# M900.net
KiCad netlist of a schematic drawn in EAGLE
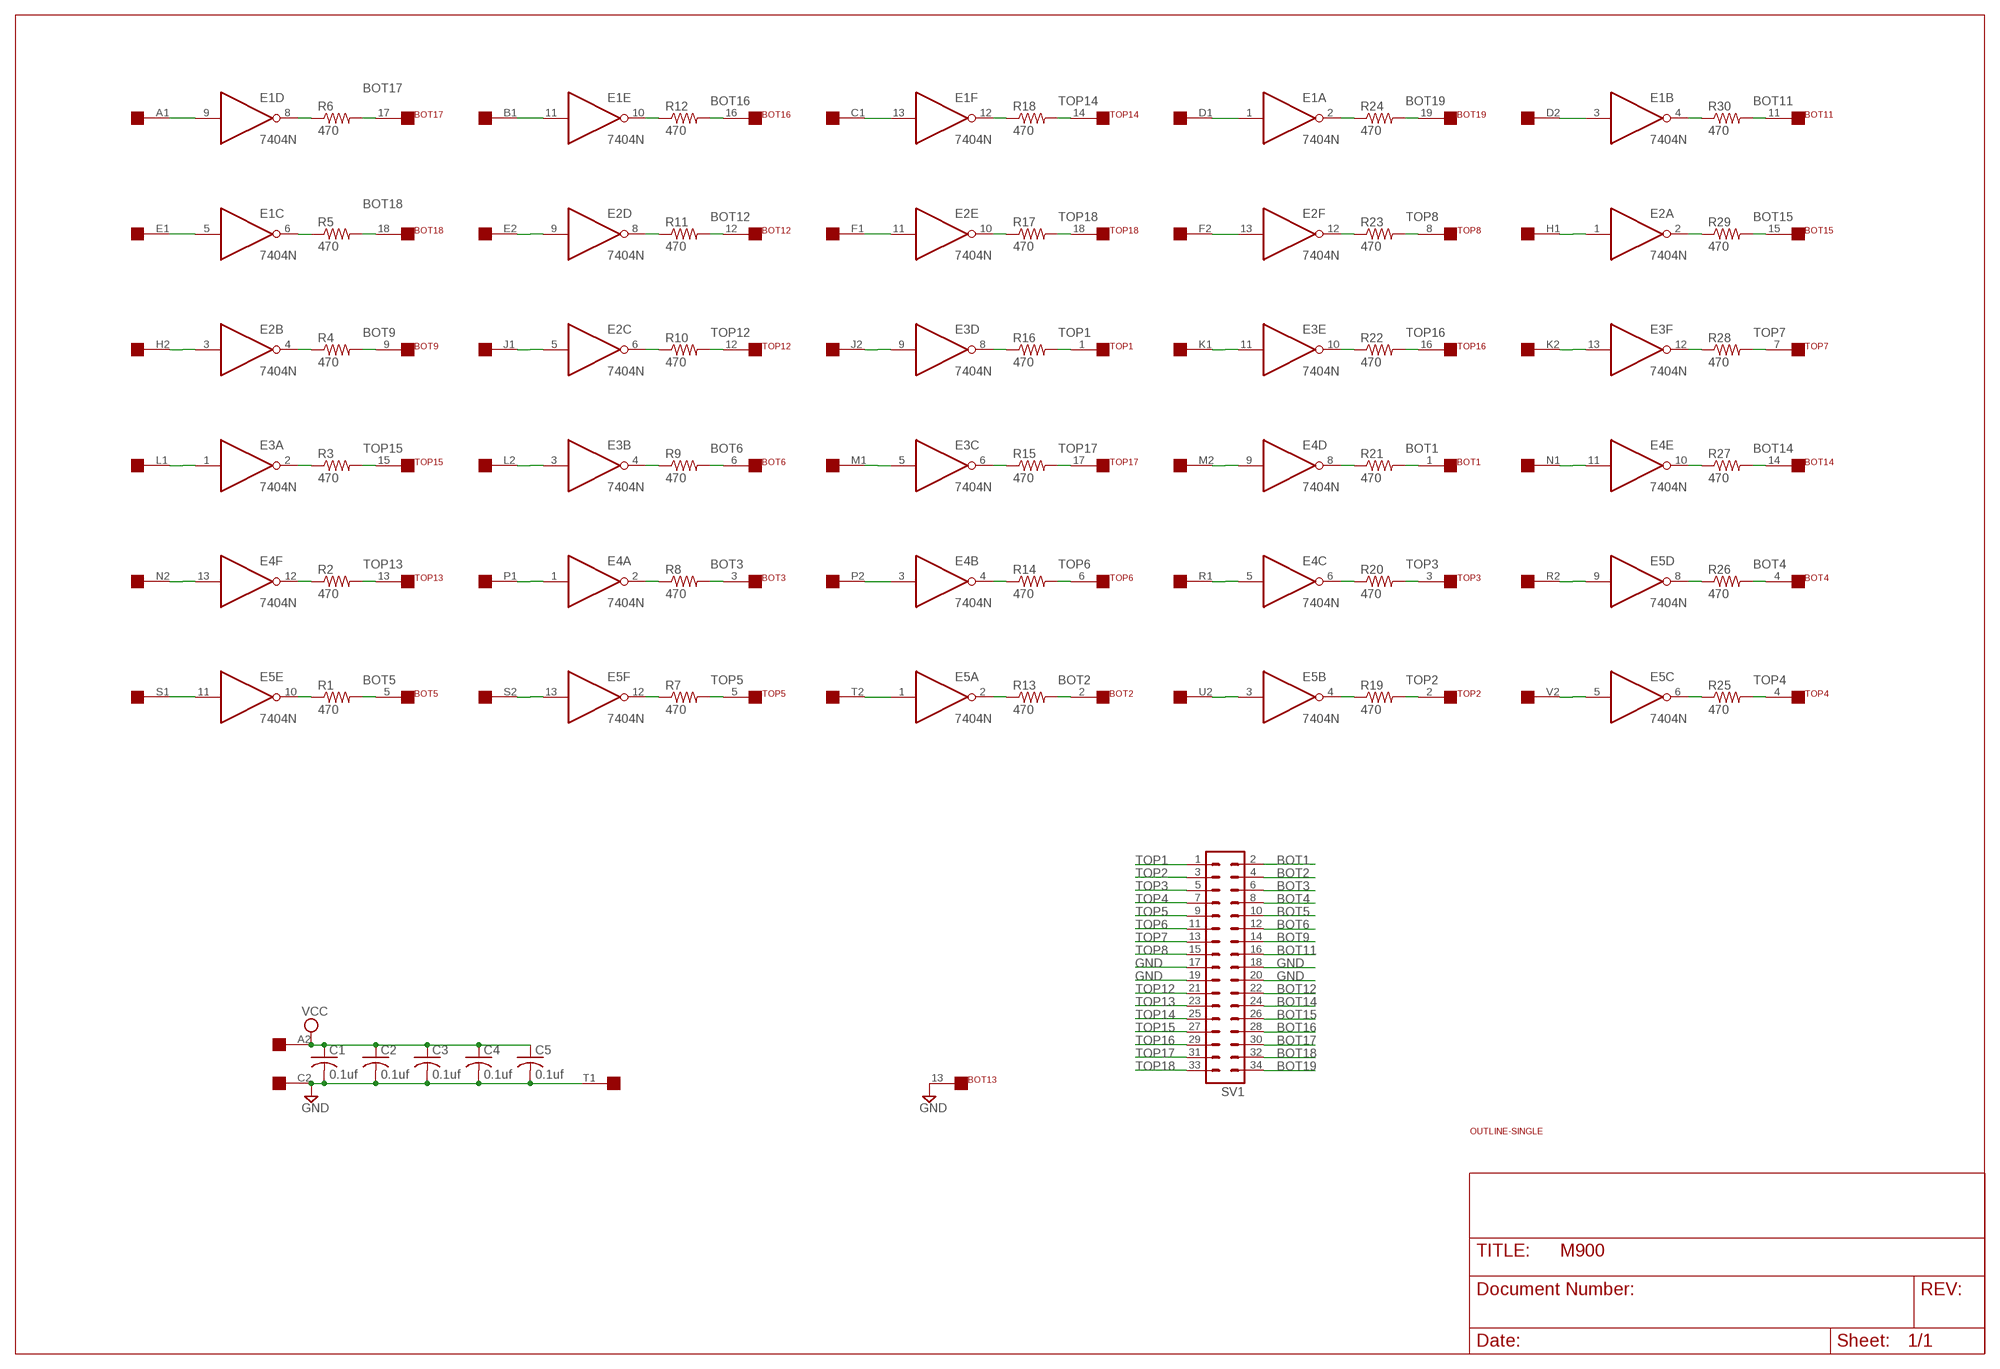
[diagram p0: schematic, sheet 1]

(export (version "E")
  (design (tool "Eeschema 10.0.6"))
  (components
    (comp (ref "BOT")
      (value "FLEX19")
      (footprint "eagle-import:FLEX19")
      (libsource (lib "eagle-import") (part "FLEX19"))
    )
    (comp (ref "C1")
      (value "0.1uf")
      (footprint "eagle-import:C050-025X075")
      (libsource (lib "eagle-import") (part "C-US050-025X075"))
    )
    (comp (ref "C2")
      (value "0.1uf")
      (footprint "eagle-import:C050-025X075")
      (libsource (lib "eagle-import") (part "C-US050-025X075"))
    )
    (comp (ref "C3")
      (value "0.1uf")
      (footprint "eagle-import:C050-025X075")
      (libsource (lib "eagle-import") (part "C-US050-025X075"))
    )
    (comp (ref "C4")
      (value "0.1uf")
      (footprint "eagle-import:C050-025X075")
      (libsource (lib "eagle-import") (part "C-US050-025X075"))
    )
    (comp (ref "C5")
      (value "0.1uf")
      (footprint "eagle-import:C050-025X075")
      (libsource (lib "eagle-import") (part "C-US050-025X075"))
    )
    (comp (ref "E1")
      (value "7404N")
      (footprint "eagle-import:DIL14")
      (libsource (lib "eagle-import") (part "7404N"))
    )
    (comp (ref "E2")
      (value "7404N")
      (footprint "eagle-import:DIL14")
      (libsource (lib "eagle-import") (part "7404N"))
    )
    (comp (ref "E3")
      (value "7404N")
      (footprint "eagle-import:DIL14")
      (libsource (lib "eagle-import") (part "7404N"))
    )
    (comp (ref "E4")
      (value "7404N")
      (footprint "eagle-import:DIL14")
      (libsource (lib "eagle-import") (part "7404N"))
    )
    (comp (ref "E5")
      (value "7404N")
      (footprint "eagle-import:DIL14")
      (libsource (lib "eagle-import") (part "7404N"))
    )
    (comp (ref "EDGE")
      (value "SINGLE")
      (footprint "eagle-import:EDGE-CON2")
      (libsource (lib "eagle-import") (part "SINGLE"))
    )
    (comp (ref "R1")
      (value "470")
      (footprint "eagle-import:0207_10")
      (libsource (lib "eagle-import") (part "R-US_0207/10"))
    )
    (comp (ref "R2")
      (value "470")
      (footprint "eagle-import:0207_10")
      (libsource (lib "eagle-import") (part "R-US_0207/10"))
    )
    (comp (ref "R3")
      (value "470")
      (footprint "eagle-import:0207_10")
      (libsource (lib "eagle-import") (part "R-US_0207/10"))
    )
    (comp (ref "R4")
      (value "470")
      (footprint "eagle-import:0207_10")
      (libsource (lib "eagle-import") (part "R-US_0207/10"))
    )
    (comp (ref "R5")
      (value "470")
      (footprint "eagle-import:0207_10")
      (libsource (lib "eagle-import") (part "R-US_0207/10"))
    )
    (comp (ref "R6")
      (value "470")
      (footprint "eagle-import:0207_10")
      (libsource (lib "eagle-import") (part "R-US_0207/10"))
    )
    (comp (ref "R7")
      (value "470")
      (footprint "eagle-import:0207_10")
      (libsource (lib "eagle-import") (part "R-US_0207/10"))
    )
    (comp (ref "R8")
      (value "470")
      (footprint "eagle-import:0207_10")
      (libsource (lib "eagle-import") (part "R-US_0207/10"))
    )
    (comp (ref "R9")
      (value "470")
      (footprint "eagle-import:0207_10")
      (libsource (lib "eagle-import") (part "R-US_0207/10"))
    )
    (comp (ref "R10")
      (value "470")
      (footprint "eagle-import:0207_10")
      (libsource (lib "eagle-import") (part "R-US_0207/10"))
    )
    (comp (ref "R11")
      (value "470")
      (footprint "eagle-import:0207_10")
      (libsource (lib "eagle-import") (part "R-US_0207/10"))
    )
    (comp (ref "R12")
      (value "470")
      (footprint "eagle-import:0207_10")
      (libsource (lib "eagle-import") (part "R-US_0207/10"))
    )
    (comp (ref "R13")
      (value "470")
      (footprint "eagle-import:0207_10")
      (libsource (lib "eagle-import") (part "R-US_0207/10"))
    )
    (comp (ref "R14")
      (value "470")
      (footprint "eagle-import:0207_10")
      (libsource (lib "eagle-import") (part "R-US_0207/10"))
    )
    (comp (ref "R15")
      (value "470")
      (footprint "eagle-import:0207_10")
      (libsource (lib "eagle-import") (part "R-US_0207/10"))
    )
    (comp (ref "R16")
      (value "470")
      (footprint "eagle-import:0207_10")
      (libsource (lib "eagle-import") (part "R-US_0207/10"))
    )
    (comp (ref "R17")
      (value "470")
      (footprint "eagle-import:0207_10")
      (libsource (lib "eagle-import") (part "R-US_0207/10"))
    )
    (comp (ref "R18")
      (value "470")
      (footprint "eagle-import:0207_10")
      (libsource (lib "eagle-import") (part "R-US_0207/10"))
    )
    (comp (ref "R19")
      (value "470")
      (footprint "eagle-import:0207_10")
      (libsource (lib "eagle-import") (part "R-US_0207/10"))
    )
    (comp (ref "R20")
      (value "470")
      (footprint "eagle-import:0207_10")
      (libsource (lib "eagle-import") (part "R-US_0207/10"))
    )
    (comp (ref "R21")
      (value "470")
      (footprint "eagle-import:0207_10")
      (libsource (lib "eagle-import") (part "R-US_0207/10"))
    )
    (comp (ref "R22")
      (value "470")
      (footprint "eagle-import:0207_10")
      (libsource (lib "eagle-import") (part "R-US_0207/10"))
    )
    (comp (ref "R23")
      (value "470")
      (footprint "eagle-import:0207_10")
      (libsource (lib "eagle-import") (part "R-US_0207/10"))
    )
    (comp (ref "R24")
      (value "470")
      (footprint "eagle-import:0207_10")
      (libsource (lib "eagle-import") (part "R-US_0207/10"))
    )
    (comp (ref "R25")
      (value "470")
      (footprint "eagle-import:0207_10")
      (libsource (lib "eagle-import") (part "R-US_0207/10"))
    )
    (comp (ref "R26")
      (value "470")
      (footprint "eagle-import:0207_10")
      (libsource (lib "eagle-import") (part "R-US_0207/10"))
    )
    (comp (ref "R27")
      (value "470")
      (footprint "eagle-import:0207_10")
      (libsource (lib "eagle-import") (part "R-US_0207/10"))
    )
    (comp (ref "R28")
      (value "470")
      (footprint "eagle-import:0207_10")
      (libsource (lib "eagle-import") (part "R-US_0207/10"))
    )
    (comp (ref "R29")
      (value "470")
      (footprint "eagle-import:0207_10")
      (libsource (lib "eagle-import") (part "R-US_0207/10"))
    )
    (comp (ref "R30")
      (value "470")
      (footprint "eagle-import:0207_10")
      (libsource (lib "eagle-import") (part "R-US_0207/10"))
    )
    (comp (ref "SV1")
      (value "MA17-2")
      (footprint "eagle-import:MA17-2")
      (libsource (lib "eagle-import") (part "MA17-2"))
    )
    (comp (ref "TOP")
      (value "FLEX19")
      (footprint "eagle-import:FLEX19")
      (libsource (lib "eagle-import") (part "FLEX19"))
    )
    (comp (ref "U$2")
      (value "OUTLINE-SINGLE")
      (footprint "eagle-import:SINGLE")
      (libsource (lib "eagle-import") (part "OUTLINE-SINGLE"))
    )
  )
  (nets
    (net (code "1") (name "/BOT1") (class "Default")
      (node (ref "BOT") (pin "1") (pinfunction "1_1") (pintype "passive"))
      (node (ref "R21") (pin "2") (pinfunction "2_2") (pintype "passive"))
      (node (ref "SV1") (pin "2") (pinfunction "2_2") (pintype "passive"))
    )
    (net (code "2") (name "/BOT2") (class "Default")
      (node (ref "BOT") (pin "2") (pinfunction "1_2") (pintype "passive"))
      (node (ref "R13") (pin "2") (pinfunction "2_2") (pintype "passive"))
      (node (ref "SV1") (pin "4") (pinfunction "4_4") (pintype "passive"))
    )
    (net (code "3") (name "/BOT3") (class "Default")
      (node (ref "BOT") (pin "3") (pinfunction "1_3") (pintype "passive"))
      (node (ref "R8") (pin "2") (pinfunction "2_2") (pintype "passive"))
      (node (ref "SV1") (pin "6") (pinfunction "6_6") (pintype "passive"))
    )
    (net (code "4") (name "/BOT4") (class "Default")
      (node (ref "BOT") (pin "4") (pinfunction "1_4") (pintype "passive"))
      (node (ref "R26") (pin "2") (pinfunction "2_2") (pintype "passive"))
      (node (ref "SV1") (pin "8") (pinfunction "8_8") (pintype "passive"))
    )
    (net (code "5") (name "/BOT5") (class "Default")
      (node (ref "BOT") (pin "5") (pinfunction "1_5") (pintype "passive"))
      (node (ref "R1") (pin "2") (pinfunction "2_2") (pintype "passive"))
      (node (ref "SV1") (pin "10") (pinfunction "10_10") (pintype "passive"))
    )
    (net (code "6") (name "/BOT6") (class "Default")
      (node (ref "BOT") (pin "6") (pinfunction "1_6") (pintype "passive"))
      (node (ref "R9") (pin "2") (pinfunction "2_2") (pintype "passive"))
      (node (ref "SV1") (pin "12") (pinfunction "12_12") (pintype "passive"))
    )
    (net (code "7") (name "/BOT9") (class "Default")
      (node (ref "BOT") (pin "9") (pinfunction "1_9") (pintype "passive"))
      (node (ref "R4") (pin "2") (pinfunction "2_2") (pintype "passive"))
      (node (ref "SV1") (pin "14") (pinfunction "14_14") (pintype "passive"))
    )
    (net (code "8") (name "/BOT11") (class "Default")
      (node (ref "BOT") (pin "11") (pinfunction "1_11") (pintype "passive"))
      (node (ref "R30") (pin "2") (pinfunction "2_2") (pintype "passive"))
      (node (ref "SV1") (pin "16") (pinfunction "16_16") (pintype "passive"))
    )
    (net (code "9") (name "/BOT12") (class "Default")
      (node (ref "BOT") (pin "12") (pinfunction "1_12") (pintype "passive"))
      (node (ref "R11") (pin "2") (pinfunction "2_2") (pintype "passive"))
      (node (ref "SV1") (pin "22") (pinfunction "22_22") (pintype "passive"))
    )
    (net (code "10") (name "/BOT14") (class "Default")
      (node (ref "BOT") (pin "14") (pinfunction "1_14") (pintype "passive"))
      (node (ref "R27") (pin "2") (pinfunction "2_2") (pintype "passive"))
      (node (ref "SV1") (pin "24") (pinfunction "24_24") (pintype "passive"))
    )
    (net (code "11") (name "/BOT15") (class "Default")
      (node (ref "BOT") (pin "15") (pinfunction "1_15") (pintype "passive"))
      (node (ref "R29") (pin "2") (pinfunction "2_2") (pintype "passive"))
      (node (ref "SV1") (pin "26") (pinfunction "26_26") (pintype "passive"))
    )
    (net (code "12") (name "/BOT16") (class "Default")
      (node (ref "BOT") (pin "16") (pinfunction "1_16") (pintype "passive"))
      (node (ref "R12") (pin "2") (pinfunction "2_2") (pintype "passive"))
      (node (ref "SV1") (pin "28") (pinfunction "28_28") (pintype "passive"))
    )
    (net (code "13") (name "/BOT17") (class "Default")
      (node (ref "BOT") (pin "17") (pinfunction "1_17") (pintype "passive"))
      (node (ref "R6") (pin "2") (pinfunction "2_2") (pintype "passive"))
      (node (ref "SV1") (pin "30") (pinfunction "30_30") (pintype "passive"))
    )
    (net (code "14") (name "/BOT18") (class "Default")
      (node (ref "BOT") (pin "18") (pinfunction "1_18") (pintype "passive"))
      (node (ref "R5") (pin "2") (pinfunction "2_2") (pintype "passive"))
      (node (ref "SV1") (pin "32") (pinfunction "32_32") (pintype "passive"))
    )
    (net (code "15") (name "/BOT19") (class "Default")
      (node (ref "BOT") (pin "19") (pinfunction "1_19") (pintype "passive"))
      (node (ref "R24") (pin "2") (pinfunction "2_2") (pintype "passive"))
      (node (ref "SV1") (pin "34") (pinfunction "34_34") (pintype "passive"))
    )
    (net (code "16") (name "/TOP1") (class "Default")
      (node (ref "R16") (pin "2") (pinfunction "2_2") (pintype "passive"))
      (node (ref "SV1") (pin "1") (pinfunction "1_1") (pintype "passive"))
      (node (ref "TOP") (pin "1") (pinfunction "1_1") (pintype "passive"))
    )
    (net (code "17") (name "/TOP2") (class "Default")
      (node (ref "R19") (pin "2") (pinfunction "2_2") (pintype "passive"))
      (node (ref "SV1") (pin "3") (pinfunction "3_3") (pintype "passive"))
      (node (ref "TOP") (pin "2") (pinfunction "1_2") (pintype "passive"))
    )
    (net (code "18") (name "/TOP3") (class "Default")
      (node (ref "R20") (pin "2") (pinfunction "2_2") (pintype "passive"))
      (node (ref "SV1") (pin "5") (pinfunction "5_5") (pintype "passive"))
      (node (ref "TOP") (pin "3") (pinfunction "1_3") (pintype "passive"))
    )
    (net (code "19") (name "/TOP4") (class "Default")
      (node (ref "R25") (pin "2") (pinfunction "2_2") (pintype "passive"))
      (node (ref "SV1") (pin "7") (pinfunction "7_7") (pintype "passive"))
      (node (ref "TOP") (pin "4") (pinfunction "1_4") (pintype "passive"))
    )
    (net (code "20") (name "/TOP5") (class "Default")
      (node (ref "R7") (pin "2") (pinfunction "2_2") (pintype "passive"))
      (node (ref "SV1") (pin "9") (pinfunction "9_9") (pintype "passive"))
      (node (ref "TOP") (pin "5") (pinfunction "1_5") (pintype "passive"))
    )
    (net (code "21") (name "/TOP6") (class "Default")
      (node (ref "R14") (pin "2") (pinfunction "2_2") (pintype "passive"))
      (node (ref "SV1") (pin "11") (pinfunction "11_11") (pintype "passive"))
      (node (ref "TOP") (pin "6") (pinfunction "1_6") (pintype "passive"))
    )
    (net (code "22") (name "/TOP7") (class "Default")
      (node (ref "R28") (pin "2") (pinfunction "2_2") (pintype "passive"))
      (node (ref "SV1") (pin "13") (pinfunction "13_13") (pintype "passive"))
      (node (ref "TOP") (pin "7") (pinfunction "1_7") (pintype "passive"))
    )
    (net (code "23") (name "/TOP8") (class "Default")
      (node (ref "R23") (pin "2") (pinfunction "2_2") (pintype "passive"))
      (node (ref "SV1") (pin "15") (pinfunction "15_15") (pintype "passive"))
      (node (ref "TOP") (pin "8") (pinfunction "1_8") (pintype "passive"))
    )
    (net (code "24") (name "/TOP12") (class "Default")
      (node (ref "R10") (pin "2") (pinfunction "2_2") (pintype "passive"))
      (node (ref "SV1") (pin "21") (pinfunction "21_21") (pintype "passive"))
      (node (ref "TOP") (pin "12") (pinfunction "1_12") (pintype "passive"))
    )
    (net (code "25") (name "/TOP13") (class "Default")
      (node (ref "R2") (pin "2") (pinfunction "2_2") (pintype "passive"))
      (node (ref "SV1") (pin "23") (pinfunction "23_23") (pintype "passive"))
      (node (ref "TOP") (pin "13") (pinfunction "1_13") (pintype "passive"))
    )
    (net (code "26") (name "/TOP14") (class "Default")
      (node (ref "R18") (pin "2") (pinfunction "2_2") (pintype "passive"))
      (node (ref "SV1") (pin "25") (pinfunction "25_25") (pintype "passive"))
      (node (ref "TOP") (pin "14") (pinfunction "1_14") (pintype "passive"))
    )
    (net (code "27") (name "/TOP15") (class "Default")
      (node (ref "R3") (pin "2") (pinfunction "2_2") (pintype "passive"))
      (node (ref "SV1") (pin "27") (pinfunction "27_27") (pintype "passive"))
      (node (ref "TOP") (pin "15") (pinfunction "1_15") (pintype "passive"))
    )
    (net (code "28") (name "/TOP16") (class "Default")
      (node (ref "R22") (pin "2") (pinfunction "2_2") (pintype "passive"))
      (node (ref "SV1") (pin "29") (pinfunction "29_29") (pintype "passive"))
      (node (ref "TOP") (pin "16") (pinfunction "1_16") (pintype "passive"))
    )
    (net (code "29") (name "/TOP17") (class "Default")
      (node (ref "R15") (pin "2") (pinfunction "2_2") (pintype "passive"))
      (node (ref "SV1") (pin "31") (pinfunction "31_31") (pintype "passive"))
      (node (ref "TOP") (pin "17") (pinfunction "1_17") (pintype "passive"))
    )
    (net (code "30") (name "/TOP18") (class "Default")
      (node (ref "R17") (pin "2") (pinfunction "2_2") (pintype "passive"))
      (node (ref "SV1") (pin "33") (pinfunction "33_33") (pintype "passive"))
      (node (ref "TOP") (pin "18") (pinfunction "1_18") (pintype "passive"))
    )
    (net (code "31") (name "GND") (class "Default")
      (node (ref "BOT") (pin "13") (pinfunction "1_13") (pintype "passive"))
      (node (ref "C1") (pin "2") (pinfunction "2_2") (pintype "passive"))
      (node (ref "C2") (pin "2") (pinfunction "2_2") (pintype "passive"))
      (node (ref "C3") (pin "2") (pinfunction "2_2") (pintype "passive"))
      (node (ref "C4") (pin "2") (pinfunction "2_2") (pintype "passive"))
      (node (ref "C5") (pin "2") (pinfunction "2_2") (pintype "passive"))
      (node (ref "EDGE") (pin "C2") (pinfunction "1_C2") (pintype "bidirectional"))
      (node (ref "EDGE") (pin "T1") (pinfunction "1_T1") (pintype "bidirectional"))
      (node (ref "SV1") (pin "17") (pinfunction "17_17") (pintype "passive"))
      (node (ref "SV1") (pin "18") (pinfunction "18_18") (pintype "passive"))
      (node (ref "SV1") (pin "19") (pinfunction "19_19") (pintype "passive"))
      (node (ref "SV1") (pin "20") (pinfunction "20_20") (pintype "passive"))
    )
    (net (code "32") (name "Net-(E1A-I)") (class "Default")
      (node (ref "E1") (pin "1") (pinfunction "I_1") (pintype "input"))
      (node (ref "EDGE") (pin "D1") (pinfunction "1_D1") (pintype "bidirectional"))
    )
    (net (code "33") (name "Net-(E1A-O)") (class "Default")
      (node (ref "E1") (pin "2") (pinfunction "O_2") (pintype "output"))
      (node (ref "R24") (pin "1") (pinfunction "1_1") (pintype "passive"))
    )
    (net (code "34") (name "Net-(E1B-I)") (class "Default")
      (node (ref "E1") (pin "3") (pinfunction "I_3") (pintype "input"))
      (node (ref "EDGE") (pin "D2") (pinfunction "1_D2") (pintype "bidirectional"))
    )
    (net (code "35") (name "Net-(E1B-O)") (class "Default")
      (node (ref "E1") (pin "4") (pinfunction "O_4") (pintype "output"))
      (node (ref "R30") (pin "1") (pinfunction "1_1") (pintype "passive"))
    )
    (net (code "36") (name "Net-(E1C-I)") (class "Default")
      (node (ref "E1") (pin "5") (pinfunction "I_5") (pintype "input"))
      (node (ref "EDGE") (pin "E1") (pinfunction "1_E1") (pintype "bidirectional"))
    )
    (net (code "37") (name "Net-(E1C-O)") (class "Default")
      (node (ref "E1") (pin "6") (pinfunction "O_6") (pintype "output"))
      (node (ref "R5") (pin "1") (pinfunction "1_1") (pintype "passive"))
    )
    (net (code "38") (name "Net-(E1D-I)") (class "Default")
      (node (ref "E1") (pin "9") (pinfunction "I_9") (pintype "input"))
      (node (ref "EDGE") (pin "A1") (pinfunction "1_A1") (pintype "bidirectional"))
    )
    (net (code "39") (name "Net-(E1D-O)") (class "Default")
      (node (ref "E1") (pin "8") (pinfunction "O_8") (pintype "output"))
      (node (ref "R6") (pin "1") (pinfunction "1_1") (pintype "passive"))
    )
    (net (code "40") (name "Net-(E1E-I)") (class "Default")
      (node (ref "E1") (pin "11") (pinfunction "I_11") (pintype "input"))
      (node (ref "EDGE") (pin "B1") (pinfunction "1_B1") (pintype "bidirectional"))
    )
    (net (code "41") (name "Net-(E1E-O)") (class "Default")
      (node (ref "E1") (pin "10") (pinfunction "O_10") (pintype "output"))
      (node (ref "R12") (pin "1") (pinfunction "1_1") (pintype "passive"))
    )
    (net (code "42") (name "Net-(E1F-I)") (class "Default")
      (node (ref "E1") (pin "13") (pinfunction "I_13") (pintype "input"))
      (node (ref "EDGE") (pin "C1") (pinfunction "1_C1") (pintype "bidirectional"))
    )
    (net (code "43") (name "Net-(E1F-O)") (class "Default")
      (node (ref "E1") (pin "12") (pinfunction "O_12") (pintype "output"))
      (node (ref "R18") (pin "1") (pinfunction "1_1") (pintype "passive"))
    )
    (net (code "44") (name "Net-(E2A-I)") (class "Default")
      (node (ref "E2") (pin "1") (pinfunction "I_1") (pintype "input"))
      (node (ref "EDGE") (pin "H1") (pinfunction "1_H1") (pintype "bidirectional"))
    )
    (net (code "45") (name "Net-(E2A-O)") (class "Default")
      (node (ref "E2") (pin "2") (pinfunction "O_2") (pintype "output"))
      (node (ref "R29") (pin "1") (pinfunction "1_1") (pintype "passive"))
    )
    (net (code "46") (name "Net-(E2B-I)") (class "Default")
      (node (ref "E2") (pin "3") (pinfunction "I_3") (pintype "input"))
      (node (ref "EDGE") (pin "H2") (pinfunction "1_H2") (pintype "bidirectional"))
    )
    (net (code "47") (name "Net-(E2B-O)") (class "Default")
      (node (ref "E2") (pin "4") (pinfunction "O_4") (pintype "output"))
      (node (ref "R4") (pin "1") (pinfunction "1_1") (pintype "passive"))
    )
    (net (code "48") (name "Net-(E2C-I)") (class "Default")
      (node (ref "E2") (pin "5") (pinfunction "I_5") (pintype "input"))
      (node (ref "EDGE") (pin "J1") (pinfunction "1_J1") (pintype "bidirectional"))
    )
    (net (code "49") (name "Net-(E2C-O)") (class "Default")
      (node (ref "E2") (pin "6") (pinfunction "O_6") (pintype "output"))
      (node (ref "R10") (pin "1") (pinfunction "1_1") (pintype "passive"))
    )
    (net (code "50") (name "Net-(E2D-I)") (class "Default")
      (node (ref "E2") (pin "9") (pinfunction "I_9") (pintype "input"))
      (node (ref "EDGE") (pin "E2") (pinfunction "1_E2") (pintype "bidirectional"))
    )
    (net (code "51") (name "Net-(E2D-O)") (class "Default")
      (node (ref "E2") (pin "8") (pinfunction "O_8") (pintype "output"))
      (node (ref "R11") (pin "1") (pinfunction "1_1") (pintype "passive"))
    )
    (net (code "52") (name "Net-(E2E-I)") (class "Default")
      (node (ref "E2") (pin "11") (pinfunction "I_11") (pintype "input"))
      (node (ref "EDGE") (pin "F1") (pinfunction "1_F1") (pintype "bidirectional"))
    )
    (net (code "53") (name "Net-(E2E-O)") (class "Default")
      (node (ref "E2") (pin "10") (pinfunction "O_10") (pintype "output"))
      (node (ref "R17") (pin "1") (pinfunction "1_1") (pintype "passive"))
    )
    (net (code "54") (name "Net-(E2F-I)") (class "Default")
      (node (ref "E2") (pin "13") (pinfunction "I_13") (pintype "input"))
      (node (ref "EDGE") (pin "F2") (pinfunction "1_F2") (pintype "bidirectional"))
    )
    (net (code "55") (name "Net-(E2F-O)") (class "Default")
      (node (ref "E2") (pin "12") (pinfunction "O_12") (pintype "output"))
      (node (ref "R23") (pin "1") (pinfunction "1_1") (pintype "passive"))
    )
    (net (code "56") (name "Net-(E3A-I)") (class "Default")
      (node (ref "E3") (pin "1") (pinfunction "I_1") (pintype "input"))
      (node (ref "EDGE") (pin "L1") (pinfunction "1_L1") (pintype "bidirectional"))
    )
    (net (code "57") (name "Net-(E3A-O)") (class "Default")
      (node (ref "E3") (pin "2") (pinfunction "O_2") (pintype "output"))
      (node (ref "R3") (pin "1") (pinfunction "1_1") (pintype "passive"))
    )
    (net (code "58") (name "Net-(E3B-I)") (class "Default")
      (node (ref "E3") (pin "3") (pinfunction "I_3") (pintype "input"))
      (node (ref "EDGE") (pin "L2") (pinfunction "1_L2") (pintype "bidirectional"))
    )
    (net (code "59") (name "Net-(E3B-O)") (class "Default")
      (node (ref "E3") (pin "4") (pinfunction "O_4") (pintype "output"))
      (node (ref "R9") (pin "1") (pinfunction "1_1") (pintype "passive"))
    )
    (net (code "60") (name "Net-(E3C-I)") (class "Default")
      (node (ref "E3") (pin "5") (pinfunction "I_5") (pintype "input"))
      (node (ref "EDGE") (pin "M1") (pinfunction "1_M1") (pintype "bidirectional"))
    )
    (net (code "61") (name "Net-(E3C-O)") (class "Default")
      (node (ref "E3") (pin "6") (pinfunction "O_6") (pintype "output"))
      (node (ref "R15") (pin "1") (pinfunction "1_1") (pintype "passive"))
    )
    (net (code "62") (name "Net-(E3D-I)") (class "Default")
      (node (ref "E3") (pin "9") (pinfunction "I_9") (pintype "input"))
      (node (ref "EDGE") (pin "J2") (pinfunction "1_J2") (pintype "bidirectional"))
    )
    (net (code "63") (name "Net-(E3D-O)") (class "Default")
      (node (ref "E3") (pin "8") (pinfunction "O_8") (pintype "output"))
      (node (ref "R16") (pin "1") (pinfunction "1_1") (pintype "passive"))
    )
    (net (code "64") (name "Net-(E3E-I)") (class "Default")
      (node (ref "E3") (pin "11") (pinfunction "I_11") (pintype "input"))
      (node (ref "EDGE") (pin "K1") (pinfunction "1_K1") (pintype "bidirectional"))
    )
    (net (code "65") (name "Net-(E3E-O)") (class "Default")
      (node (ref "E3") (pin "10") (pinfunction "O_10") (pintype "output"))
      (node (ref "R22") (pin "1") (pinfunction "1_1") (pintype "passive"))
    )
    (net (code "66") (name "Net-(E3F-I)") (class "Default")
      (node (ref "E3") (pin "13") (pinfunction "I_13") (pintype "input"))
      (node (ref "EDGE") (pin "K2") (pinfunction "1_K2") (pintype "bidirectional"))
    )
    (net (code "67") (name "Net-(E3F-O)") (class "Default")
      (node (ref "E3") (pin "12") (pinfunction "O_12") (pintype "output"))
      (node (ref "R28") (pin "1") (pinfunction "1_1") (pintype "passive"))
    )
    (net (code "68") (name "Net-(E4A-I)") (class "Default")
      (node (ref "E4") (pin "1") (pinfunction "I_1") (pintype "input"))
      (node (ref "EDGE") (pin "P1") (pinfunction "1_P1") (pintype "bidirectional"))
    )
    (net (code "69") (name "Net-(E4A-O)") (class "Default")
      (node (ref "E4") (pin "2") (pinfunction "O_2") (pintype "output"))
      (node (ref "R8") (pin "1") (pinfunction "1_1") (pintype "passive"))
    )
    (net (code "70") (name "Net-(E4B-I)") (class "Default")
      (node (ref "E4") (pin "3") (pinfunction "I_3") (pintype "input"))
      (node (ref "EDGE") (pin "P2") (pinfunction "1_P2") (pintype "bidirectional"))
    )
    (net (code "71") (name "Net-(E4B-O)") (class "Default")
      (node (ref "E4") (pin "4") (pinfunction "O_4") (pintype "output"))
      (node (ref "R14") (pin "1") (pinfunction "1_1") (pintype "passive"))
    )
    (net (code "72") (name "Net-(E4C-I)") (class "Default")
      (node (ref "E4") (pin "5") (pinfunction "I_5") (pintype "input"))
      (node (ref "EDGE") (pin "R1") (pinfunction "1_R1") (pintype "bidirectional"))
    )
    (net (code "73") (name "Net-(E4C-O)") (class "Default")
      (node (ref "E4") (pin "6") (pinfunction "O_6") (pintype "output"))
      (node (ref "R20") (pin "1") (pinfunction "1_1") (pintype "passive"))
    )
    (net (code "74") (name "Net-(E4D-I)") (class "Default")
      (node (ref "E4") (pin "9") (pinfunction "I_9") (pintype "input"))
      (node (ref "EDGE") (pin "M2") (pinfunction "1_M2") (pintype "bidirectional"))
    )
    (net (code "75") (name "Net-(E4D-O)") (class "Default")
      (node (ref "E4") (pin "8") (pinfunction "O_8") (pintype "output"))
      (node (ref "R21") (pin "1") (pinfunction "1_1") (pintype "passive"))
    )
    (net (code "76") (name "Net-(E4E-I)") (class "Default")
      (node (ref "E4") (pin "11") (pinfunction "I_11") (pintype "input"))
      (node (ref "EDGE") (pin "N1") (pinfunction "1_N1") (pintype "bidirectional"))
    )
    (net (code "77") (name "Net-(E4E-O)") (class "Default")
      (node (ref "E4") (pin "10") (pinfunction "O_10") (pintype "output"))
      (node (ref "R27") (pin "1") (pinfunction "1_1") (pintype "passive"))
    )
    (net (code "78") (name "Net-(E4F-I)") (class "Default")
      (node (ref "E4") (pin "13") (pinfunction "I_13") (pintype "input"))
      (node (ref "EDGE") (pin "N2") (pinfunction "1_N2") (pintype "bidirectional"))
    )
    (net (code "79") (name "Net-(E4F-O)") (class "Default")
      (node (ref "E4") (pin "12") (pinfunction "O_12") (pintype "output"))
      (node (ref "R2") (pin "1") (pinfunction "1_1") (pintype "passive"))
    )
    (net (code "80") (name "Net-(E5A-I)") (class "Default")
      (node (ref "E5") (pin "1") (pinfunction "I_1") (pintype "input"))
      (node (ref "EDGE") (pin "T2") (pinfunction "1_T2") (pintype "bidirectional"))
    )
    (net (code "81") (name "Net-(E5A-O)") (class "Default")
      (node (ref "E5") (pin "2") (pinfunction "O_2") (pintype "output"))
      (node (ref "R13") (pin "1") (pinfunction "1_1") (pintype "passive"))
    )
    (net (code "82") (name "Net-(E5B-I)") (class "Default")
      (node (ref "E5") (pin "3") (pinfunction "I_3") (pintype "input"))
      (node (ref "EDGE") (pin "U2") (pinfunction "1_U2") (pintype "bidirectional"))
    )
    (net (code "83") (name "Net-(E5B-O)") (class "Default")
      (node (ref "E5") (pin "4") (pinfunction "O_4") (pintype "output"))
      (node (ref "R19") (pin "1") (pinfunction "1_1") (pintype "passive"))
    )
    (net (code "84") (name "Net-(E5C-I)") (class "Default")
      (node (ref "E5") (pin "5") (pinfunction "I_5") (pintype "input"))
      (node (ref "EDGE") (pin "V2") (pinfunction "1_V2") (pintype "bidirectional"))
    )
    (net (code "85") (name "Net-(E5C-O)") (class "Default")
      (node (ref "E5") (pin "6") (pinfunction "O_6") (pintype "output"))
      (node (ref "R25") (pin "1") (pinfunction "1_1") (pintype "passive"))
    )
    (net (code "86") (name "Net-(E5D-I)") (class "Default")
      (node (ref "E5") (pin "9") (pinfunction "I_9") (pintype "input"))
      (node (ref "EDGE") (pin "R2") (pinfunction "1_R2") (pintype "bidirectional"))
    )
    (net (code "87") (name "Net-(E5D-O)") (class "Default")
      (node (ref "E5") (pin "8") (pinfunction "O_8") (pintype "output"))
      (node (ref "R26") (pin "1") (pinfunction "1_1") (pintype "passive"))
    )
    (net (code "88") (name "Net-(E5E-I)") (class "Default")
      (node (ref "E5") (pin "11") (pinfunction "I_11") (pintype "input"))
      (node (ref "EDGE") (pin "S1") (pinfunction "1_S1") (pintype "bidirectional"))
    )
    (net (code "89") (name "Net-(E5E-O)") (class "Default")
      (node (ref "E5") (pin "10") (pinfunction "O_10") (pintype "output"))
      (node (ref "R1") (pin "1") (pinfunction "1_1") (pintype "passive"))
    )
    (net (code "90") (name "Net-(E5F-I)") (class "Default")
      (node (ref "E5") (pin "13") (pinfunction "I_13") (pintype "input"))
      (node (ref "EDGE") (pin "S2") (pinfunction "1_S2") (pintype "bidirectional"))
    )
    (net (code "91") (name "Net-(E5F-O)") (class "Default")
      (node (ref "E5") (pin "12") (pinfunction "O_12") (pintype "output"))
      (node (ref "R7") (pin "1") (pinfunction "1_1") (pintype "passive"))
    )
    (net (code "92") (name "VCC") (class "Default")
      (node (ref "C1") (pin "1") (pinfunction "1_1") (pintype "passive"))
      (node (ref "C2") (pin "1") (pinfunction "1_1") (pintype "passive"))
      (node (ref "C3") (pin "1") (pinfunction "1_1") (pintype "passive"))
      (node (ref "C4") (pin "1") (pinfunction "1_1") (pintype "passive"))
      (node (ref "C5") (pin "1") (pinfunction "1_1") (pintype "passive"))
      (node (ref "EDGE") (pin "A2") (pinfunction "1_A2") (pintype "bidirectional"))
    )
  )
)
